# DragonBreakout.net
KiCad netlist of a schematic drawn in EAGLE
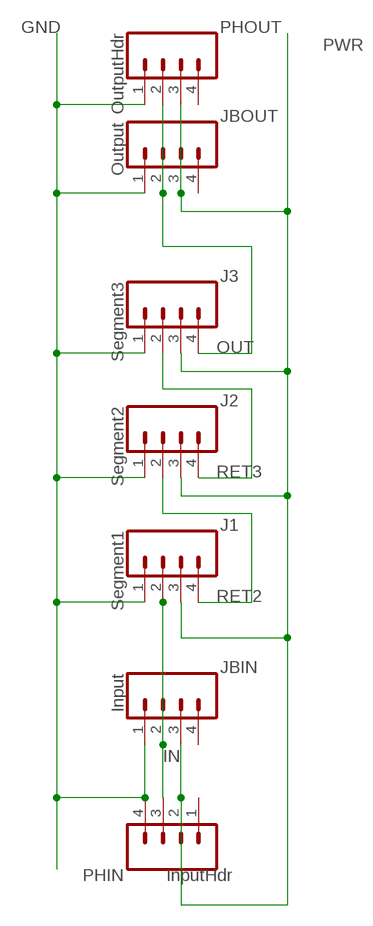
[diagram p0: schematic, sheet 1]

(export (version "E")
  (design (tool "Eeschema 10.0.6"))
  (components
    (comp (ref "J1")
      (value "Segment1")
      (footprint "eagle-import:SCREWTERMINAL-3.5MM-4_LOCK")
      (libsource (lib "eagle-import") (part "CONN_04SCREW_LOCK"))
    )
    (comp (ref "J2")
      (value "Segment2")
      (footprint "eagle-import:SCREWTERMINAL-3.5MM-4_LOCK")
      (libsource (lib "eagle-import") (part "CONN_04SCREW_LOCK"))
    )
    (comp (ref "J3")
      (value "Segment3")
      (footprint "eagle-import:SCREWTERMINAL-3.5MM-4_LOCK")
      (libsource (lib "eagle-import") (part "CONN_04SCREW_LOCK"))
    )
    (comp (ref "JBIN")
      (value "Input")
      (footprint "eagle-import:SCREWTERMINAL-3.5MM-4_LOCK")
      (libsource (lib "eagle-import") (part "CONN_04SCREW_LOCK"))
    )
    (comp (ref "JBOUT")
      (value "Output")
      (footprint "eagle-import:SCREWTERMINAL-3.5MM-4_LOCK")
      (libsource (lib "eagle-import") (part "CONN_04SCREW_LOCK"))
    )
    (comp (ref "PHIN")
      (value "InputHdr")
      (footprint "eagle-import:1X04")
      (libsource (lib "eagle-import") (part "CONN_04PTH"))
    )
    (comp (ref "PHOUT")
      (value "OutputHdr")
      (footprint "eagle-import:1X04")
      (libsource (lib "eagle-import") (part "CONN_04PTH"))
    )
  )
  (nets
    (net (code "1") (name "/GND") (class "Default")
      (node (ref "J1") (pin "1") (pinfunction "1_1") (pintype "passive"))
      (node (ref "J2") (pin "1") (pinfunction "1_1") (pintype "passive"))
      (node (ref "J3") (pin "1") (pinfunction "1_1") (pintype "passive"))
      (node (ref "JBIN") (pin "1") (pinfunction "1_1") (pintype "passive"))
      (node (ref "JBOUT") (pin "1") (pinfunction "1_1") (pintype "passive"))
      (node (ref "PHIN") (pin "4") (pinfunction "4_4") (pintype "passive"))
      (node (ref "PHOUT") (pin "1") (pinfunction "1_1") (pintype "passive"))
    )
    (net (code "2") (name "/IN") (class "Default")
      (node (ref "J1") (pin "2") (pinfunction "2_2") (pintype "passive"))
      (node (ref "JBIN") (pin "2") (pinfunction "2_2") (pintype "passive"))
      (node (ref "PHIN") (pin "3") (pinfunction "3_3") (pintype "passive"))
    )
    (net (code "3") (name "/OUT") (class "Default")
      (node (ref "J3") (pin "4") (pinfunction "4_4") (pintype "passive"))
      (node (ref "JBOUT") (pin "2") (pinfunction "2_2") (pintype "passive"))
      (node (ref "PHOUT") (pin "2") (pinfunction "2_2") (pintype "passive"))
    )
    (net (code "4") (name "/PWR") (class "Default")
      (node (ref "J1") (pin "3") (pinfunction "3_3") (pintype "passive"))
      (node (ref "J2") (pin "3") (pinfunction "3_3") (pintype "passive"))
      (node (ref "J3") (pin "3") (pinfunction "3_3") (pintype "passive"))
      (node (ref "JBIN") (pin "3") (pinfunction "3_3") (pintype "passive"))
      (node (ref "JBOUT") (pin "3") (pinfunction "3_3") (pintype "passive"))
      (node (ref "PHIN") (pin "2") (pinfunction "2_2") (pintype "passive"))
      (node (ref "PHOUT") (pin "3") (pinfunction "3_3") (pintype "passive"))
    )
    (net (code "5") (name "/RET2") (class "Default")
      (node (ref "J1") (pin "4") (pinfunction "4_4") (pintype "passive"))
      (node (ref "J2") (pin "2") (pinfunction "2_2") (pintype "passive"))
    )
    (net (code "6") (name "/RET3") (class "Default")
      (node (ref "J2") (pin "4") (pinfunction "4_4") (pintype "passive"))
      (node (ref "J3") (pin "2") (pinfunction "2_2") (pintype "passive"))
    )
    (net (code "7") (name "unconnected-(JBIN-Pad4)") (class "Default")
      (node (ref "JBIN") (pin "4") (pinfunction "4_4") (pintype "passive"))
    )
    (net (code "8") (name "unconnected-(JBOUT-Pad4)") (class "Default")
      (node (ref "JBOUT") (pin "4") (pinfunction "4_4") (pintype "passive"))
    )
    (net (code "9") (name "unconnected-(PHIN-Pad1)") (class "Default")
      (node (ref "PHIN") (pin "1") (pinfunction "1_1") (pintype "passive"))
    )
    (net (code "10") (name "unconnected-(PHOUT-Pad4)") (class "Default")
      (node (ref "PHOUT") (pin "4") (pinfunction "4_4") (pintype "passive"))
    )
  )
)
